# nizal.net
KiCad netlist of a schematic drawn in EAGLE
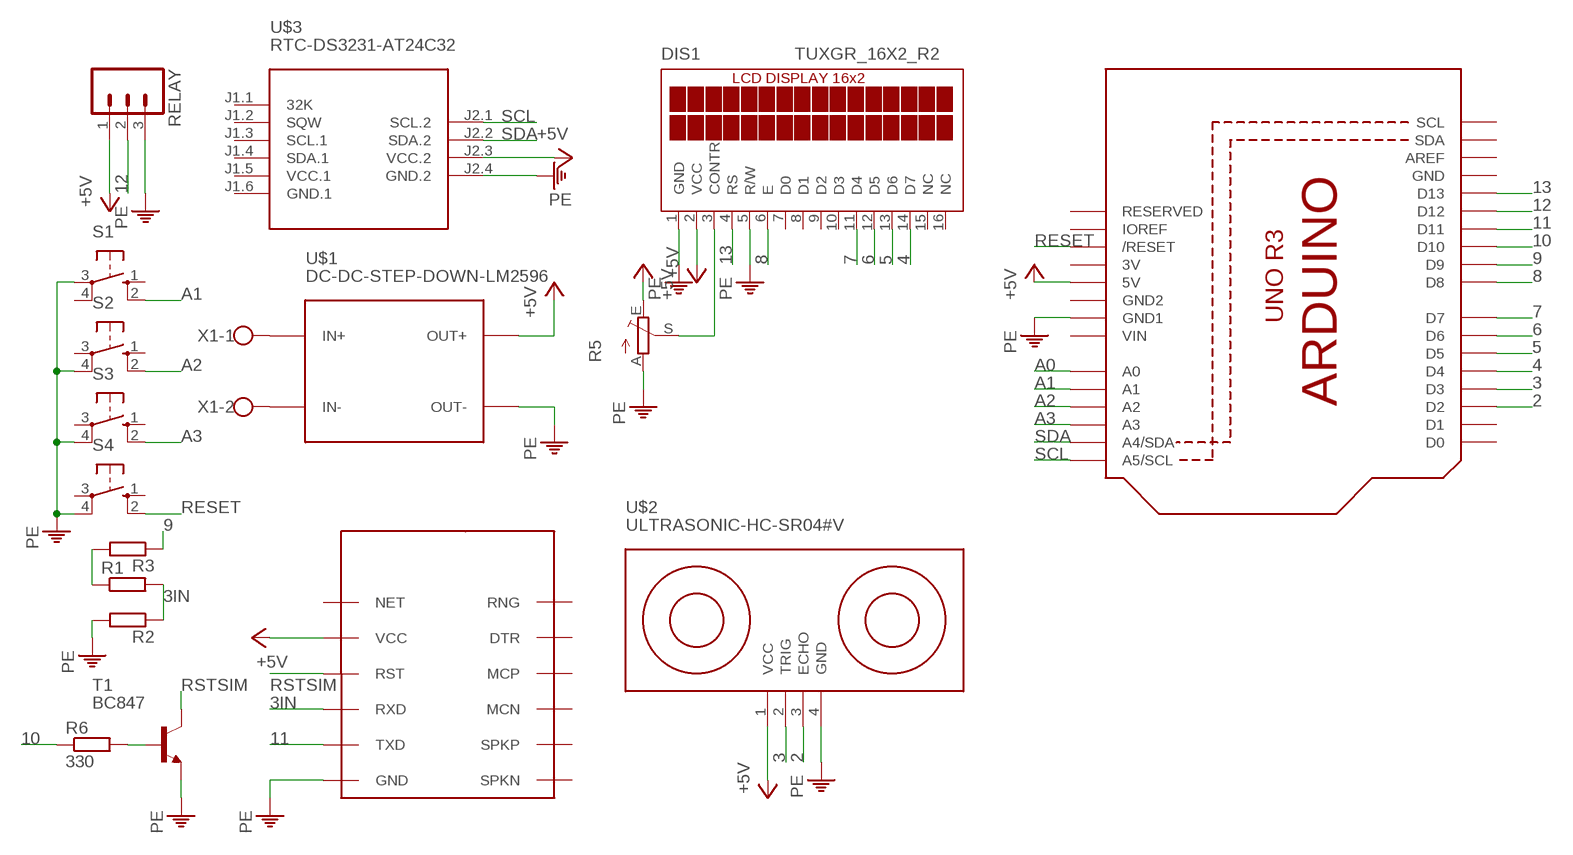
[diagram p0: schematic, sheet 1]

(export (version "E")
  (design (tool "Eeschema 10.0.6"))
  (components
    (comp (ref "DIS1")
      (value "TUXGR_16X2_R2")
      (footprint "eagle-import:TUXGR_16X2_R2")
      (libsource (lib "eagle-import") (part "TUXGR_16X2_R2"))
    )
    (comp (ref "R1")
      (value "R-EU_M0805")
      (footprint "eagle-import:M0805")
      (libsource (lib "eagle-import") (part "R-EU_M0805"))
    )
    (comp (ref "R2")
      (value "R-EU_M0805")
      (footprint "eagle-import:M0805")
      (libsource (lib "eagle-import") (part "R-EU_M0805"))
    )
    (comp (ref "R3")
      (value "R-EU_M0805")
      (footprint "eagle-import:M0805")
      (libsource (lib "eagle-import") (part "R-EU_M0805"))
    )
    (comp (ref "R5")
      (value "TRIM_EU-CA6V")
      (footprint "eagle-import:CA6V")
      (libsource (lib "eagle-import") (part "TRIM_EU-CA6V"))
    )
    (comp (ref "R6")
      (value "330")
      (footprint "eagle-import:M0805")
      (libsource (lib "eagle-import") (part "R-EU_M0805"))
    )
    (comp (ref "RELAY")
      (value "M03")
      (footprint "eagle-import:03P")
      (libsource (lib "eagle-import") (part "M03"))
    )
    (comp (ref "S1")
      (value "10-XX")
      (footprint "eagle-import:B3F-10XX")
      (fields (field (name "MPN") "B3F-1000"))
      (libsource (lib "eagle-import") (part "10-XX"))
    )
    (comp (ref "S2")
      (value "10-XX")
      (footprint "eagle-import:B3F-10XX")
      (fields (field (name "MPN") "B3F-1000"))
      (libsource (lib "eagle-import") (part "10-XX"))
    )
    (comp (ref "S3")
      (value "10-XX")
      (footprint "eagle-import:B3F-10XX")
      (fields (field (name "MPN") "B3F-1000"))
      (libsource (lib "eagle-import") (part "10-XX"))
    )
    (comp (ref "S4")
      (value "10-XX")
      (footprint "eagle-import:B3F-10XX")
      (fields (field (name "MPN") "B3F-1000"))
      (libsource (lib "eagle-import") (part "10-XX"))
    )
    (comp (ref "T1")
      (value "BC847")
      (footprint "eagle-import:SOT23")
      (libsource (lib "eagle-import") (part "BC847"))
    )
    (comp (ref "U$1")
      (value "DC-DC-STEP-DOWN-LM2596")
      (footprint "eagle-import:DC-DC-STEP-DOWN-LM2596")
      (libsource (lib "eagle-import") (part "DC-DC-STEP-DOWN-LM2596"))
    )
    (comp (ref "U$2")
      (value "ULTRASONIC-HC-SR04#V")
      (footprint "eagle-import:ULTRASONIC-HC-SR04#V")
      (libsource (lib "eagle-import") (part "ULTRASONIC-HC-SR04#V"))
    )
    (comp (ref "U$3")
      (value "RTC-DS3231-AT24C32")
      (footprint "eagle-import:RTC-DS3231-AT24C32")
      (libsource (lib "eagle-import") (part "RTC-DS3231-AT24C32"))
    )
    (comp (ref "U$4")
      (value "SIM800L")
      (footprint "eagle-import:SIM-CORE")
      (libsource (lib "eagle-import") (part "SIM800L"))
    )
    (comp (ref "U1")
      (value "ARDUINOR3-DIMENSION")
      (footprint "eagle-import:ARDUINOR3")
      (libsource (lib "eagle-import") (part "ARDUINOR3-DIMENSION"))
    )
    (comp (ref "X1")
      (value "W237-102")
      (footprint "eagle-import:W237-102")
      (fields (field (name "MPN") "237-102"))
      (libsource (lib "eagle-import") (part "W237-102"))
    )
  )
  (nets
    (net (code "1") (name "+5V") (class "Default")
      (node (ref "DIS1") (pin "2") (pinfunction "VCC_2") (pintype "power_in"))
      (node (ref "R5") (pin "E") (pinfunction "E_E") (pintype "passive"))
      (node (ref "RELAY") (pin "1") (pinfunction "1_1") (pintype "passive"))
      (node (ref "U$1") (pin "OUT+") (pinfunction "OUT+_OUT+") (pintype "bidirectional"))
      (node (ref "U$2") (pin "1") (pinfunction "VCC_1") (pintype "power_in"))
      (node (ref "U$3") (pin "J2.3") (pinfunction "VCC.2_J2.3") (pintype "power_in"))
      (node (ref "U$4") (pin "VCC") (pinfunction "VCC_VCC") (pintype "bidirectional"))
      (node (ref "U1") (pin "5V") (pinfunction "5V_5V") (pintype "power_in"))
    )
    (net (code "2") (name "/2") (class "Default")
      (node (ref "U$2") (pin "3") (pinfunction "ECHO_3") (pintype "output"))
      (node (ref "U1") (pin "D2") (pinfunction "D2_D2") (pintype "bidirectional"))
    )
    (net (code "3") (name "/3") (class "Default")
      (node (ref "U$2") (pin "2") (pinfunction "TRIG_2") (pintype "input"))
      (node (ref "U1") (pin "D3") (pinfunction "D3_D3") (pintype "bidirectional"))
    )
    (net (code "4") (name "/3IN") (class "Default")
      (node (ref "R1") (pin "2") (pinfunction "2_2") (pintype "passive"))
      (node (ref "R2") (pin "1") (pinfunction "1_1") (pintype "passive"))
      (node (ref "U$4") (pin "RXD") (pinfunction "RXD_RXD") (pintype "bidirectional"))
    )
    (net (code "5") (name "/3V") (class "Default")
      (node (ref "U1") (pin "3V") (pinfunction "3V_3V") (pintype "power_in"))
    )
    (net (code "6") (name "/4") (class "Default")
      (node (ref "DIS1") (pin "14") (pinfunction "D7_14") (pintype "input"))
      (node (ref "U1") (pin "D4") (pinfunction "D4_D4") (pintype "bidirectional"))
    )
    (net (code "7") (name "/5") (class "Default")
      (node (ref "DIS1") (pin "13") (pinfunction "D6_13") (pintype "input"))
      (node (ref "U1") (pin "D5") (pinfunction "D5_D5") (pintype "bidirectional"))
    )
    (net (code "8") (name "/6") (class "Default")
      (node (ref "DIS1") (pin "12") (pinfunction "D5_12") (pintype "input"))
      (node (ref "U1") (pin "D6") (pinfunction "D6_D6") (pintype "bidirectional"))
    )
    (net (code "9") (name "/7") (class "Default")
      (node (ref "DIS1") (pin "11") (pinfunction "D4_11") (pintype "input"))
      (node (ref "U1") (pin "D7") (pinfunction "D7_D7") (pintype "bidirectional"))
    )
    (net (code "10") (name "/8") (class "Default")
      (node (ref "DIS1") (pin "6") (pinfunction "E_6") (pintype "input"))
      (node (ref "U1") (pin "D8") (pinfunction "D8_D8") (pintype "bidirectional"))
    )
    (net (code "11") (name "/9") (class "Default")
      (node (ref "R3") (pin "1") (pinfunction "1_1") (pintype "passive"))
      (node (ref "U1") (pin "D9") (pinfunction "D9_D9") (pintype "bidirectional"))
    )
    (net (code "12") (name "/10") (class "Default")
      (node (ref "R6") (pin "1") (pinfunction "1_1") (pintype "passive"))
      (node (ref "U1") (pin "D10") (pinfunction "D10_D10") (pintype "bidirectional"))
    )
    (net (code "13") (name "/11") (class "Default")
      (node (ref "U$4") (pin "TXD") (pinfunction "TXD_TXD") (pintype "bidirectional"))
      (node (ref "U1") (pin "D11") (pinfunction "D11_D11") (pintype "bidirectional"))
    )
    (net (code "14") (name "/12") (class "Default")
      (node (ref "RELAY") (pin "2") (pinfunction "2_2") (pintype "passive"))
      (node (ref "U1") (pin "D12") (pinfunction "D12_D12") (pintype "bidirectional"))
    )
    (net (code "15") (name "/13") (class "Default")
      (node (ref "DIS1") (pin "4") (pinfunction "RS_4") (pintype "input"))
      (node (ref "U1") (pin "D13") (pinfunction "D13_D13") (pintype "bidirectional"))
    )
    (net (code "16") (name "/A0") (class "Default")
      (node (ref "U1") (pin "A0") (pinfunction "A0_A0") (pintype "bidirectional"))
    )
    (net (code "17") (name "/A1") (class "Default")
      (node (ref "S1") (pin "2") (pinfunction "S1_2") (pintype "passive"))
      (node (ref "U1") (pin "A1") (pinfunction "A1_A1") (pintype "bidirectional"))
    )
    (net (code "18") (name "/A2") (class "Default")
      (node (ref "S2") (pin "2") (pinfunction "S1_2") (pintype "passive"))
      (node (ref "U1") (pin "A2") (pinfunction "A2_A2") (pintype "bidirectional"))
    )
    (net (code "19") (name "/A3") (class "Default")
      (node (ref "S3") (pin "2") (pinfunction "S1_2") (pintype "passive"))
      (node (ref "U1") (pin "A3") (pinfunction "A3_A3") (pintype "bidirectional"))
    )
    (net (code "20") (name "/GND") (class "Default")
      (node (ref "U1") (pin "GND") (pinfunction "GND_GND") (pintype "power_in"))
    )
    (net (code "21") (name "/GND.1") (class "Default")
      (node (ref "U$3") (pin "J1.6") (pinfunction "GND.1_J1.6") (pintype "power_in"))
    )
    (net (code "22") (name "/GND2") (class "Default")
      (node (ref "U1") (pin "GND2") (pinfunction "GND2_GND2") (pintype "power_in"))
    )
    (net (code "23") (name "/RESET") (class "Default")
      (node (ref "S4") (pin "2") (pinfunction "S1_2") (pintype "passive"))
      (node (ref "U1") (pin "RESET") (pinfunction "/RESET_RESET") (pintype "bidirectional"))
    )
    (net (code "24") (name "/RSTSIM") (class "Default")
      (node (ref "T1") (pin "3") (pinfunction "C_3") (pintype "passive"))
      (node (ref "U$4") (pin "RST") (pinfunction "RST_RST") (pintype "bidirectional"))
    )
    (net (code "25") (name "/SCL") (class "Default")
      (node (ref "U$3") (pin "J2.1") (pinfunction "SCL.2_J2.1") (pintype "bidirectional"))
      (node (ref "U1") (pin "A5") (pinfunction "A5/SCL_A5") (pintype "bidirectional"))
    )
    (net (code "26") (name "/SDA") (class "Default")
      (node (ref "U$3") (pin "J2.2") (pinfunction "SDA.2_J2.2") (pintype "bidirectional"))
      (node (ref "U1") (pin "A4") (pinfunction "A4/SDA_A4") (pintype "bidirectional"))
    )
    (net (code "27") (name "/VCC.1") (class "Default")
      (node (ref "U$3") (pin "J1.5") (pinfunction "VCC.1_J1.5") (pintype "power_in"))
    )
    (net (code "28") (name "/VIN") (class "Default")
      (node (ref "U1") (pin "VIN") (pinfunction "VIN_VIN") (pintype "power_in"))
    )
    (net (code "29") (name "Net-(DIS1-CONTR)") (class "Default")
      (node (ref "DIS1") (pin "3") (pinfunction "CONTR_3") (pintype "input"))
      (node (ref "R5") (pin "S") (pinfunction "S_S") (pintype "passive"))
    )
    (net (code "30") (name "Net-(R1-Pad1)") (class "Default")
      (node (ref "R1") (pin "1") (pinfunction "1_1") (pintype "passive"))
      (node (ref "R3") (pin "2") (pinfunction "2_2") (pintype "passive"))
    )
    (net (code "31") (name "Net-(T1-B)") (class "Default")
      (node (ref "R6") (pin "2") (pinfunction "2_2") (pintype "passive"))
      (node (ref "T1") (pin "1") (pinfunction "B_1") (pintype "passive"))
    )
    (net (code "32") (name "Net-(X1A-KL)") (class "Default")
      (node (ref "U$1") (pin "IN+") (pinfunction "IN+_IN+") (pintype "bidirectional"))
      (node (ref "X1") (pin "1") (pinfunction "KL_1") (pintype "passive"))
    )
    (net (code "33") (name "Net-(X1B-KL)") (class "Default")
      (node (ref "U$1") (pin "IN-") (pinfunction "IN-_IN-") (pintype "bidirectional"))
      (node (ref "X1") (pin "2") (pinfunction "KL_2") (pintype "passive"))
    )
    (net (code "34") (name "PE") (class "Default")
      (node (ref "DIS1") (pin "1") (pinfunction "GND_1") (pintype "power_in"))
      (node (ref "DIS1") (pin "5") (pinfunction "R/W_5") (pintype "input"))
      (node (ref "R2") (pin "2") (pinfunction "2_2") (pintype "passive"))
      (node (ref "R5") (pin "A") (pinfunction "A_A") (pintype "passive"))
      (node (ref "RELAY") (pin "3") (pinfunction "3_3") (pintype "passive"))
      (node (ref "S1") (pin "3") (pinfunction "P_3") (pintype "passive"))
      (node (ref "S2") (pin "4") (pinfunction "P1_4") (pintype "passive"))
      (node (ref "S3") (pin "4") (pinfunction "P1_4") (pintype "passive"))
      (node (ref "S4") (pin "4") (pinfunction "P1_4") (pintype "passive"))
      (node (ref "T1") (pin "2") (pinfunction "E_2") (pintype "passive"))
      (node (ref "U$1") (pin "OUT-") (pinfunction "OUT-_OUT-") (pintype "bidirectional"))
      (node (ref "U$2") (pin "4") (pinfunction "GND_4") (pintype "power_in"))
      (node (ref "U$3") (pin "J2.4") (pinfunction "GND.2_J2.4") (pintype "power_in"))
      (node (ref "U$4") (pin "GND") (pinfunction "GND_GND") (pintype "bidirectional"))
      (node (ref "U1") (pin "GND1") (pinfunction "GND1_GND1") (pintype "power_in"))
    )
    (net (code "35") (name "unconnected-(DIS1-D0-Pad7)") (class "Default")
      (node (ref "DIS1") (pin "7") (pinfunction "D0_7") (pintype "input"))
    )
    (net (code "36") (name "unconnected-(DIS1-D1-Pad8)") (class "Default")
      (node (ref "DIS1") (pin "8") (pinfunction "D1_8") (pintype "input"))
    )
    (net (code "37") (name "unconnected-(DIS1-D2-Pad9)") (class "Default")
      (node (ref "DIS1") (pin "9") (pinfunction "D2_9") (pintype "input"))
    )
    (net (code "38") (name "unconnected-(DIS1-D3-Pad10)") (class "Default")
      (node (ref "DIS1") (pin "10") (pinfunction "D3_10") (pintype "input"))
    )
    (net (code "39") (name "unconnected-(DIS1-NC-Pad15)") (class "Default")
      (node (ref "DIS1") (pin "15") (pinfunction "NC_15") (pintype "no_connect"))
    )
    (net (code "40") (name "unconnected-(DIS1-NC-Pad16)") (class "Default")
      (node (ref "DIS1") (pin "16") (pinfunction "NC_16") (pintype "no_connect"))
    )
    (net (code "41") (name "unconnected-(S1-P1-Pad4)") (class "Default")
      (node (ref "S1") (pin "4") (pinfunction "P1_4") (pintype "passive"))
    )
    (net (code "42") (name "unconnected-(S1-S-Pad1)") (class "Default")
      (node (ref "S1") (pin "1") (pinfunction "S_1") (pintype "passive"))
    )
    (net (code "43") (name "unconnected-(S2-P-Pad3)") (class "Default")
      (node (ref "S2") (pin "3") (pinfunction "P_3") (pintype "passive"))
    )
    (net (code "44") (name "unconnected-(S2-S-Pad1)") (class "Default")
      (node (ref "S2") (pin "1") (pinfunction "S_1") (pintype "passive"))
    )
    (net (code "45") (name "unconnected-(S3-P-Pad3)") (class "Default")
      (node (ref "S3") (pin "3") (pinfunction "P_3") (pintype "passive"))
    )
    (net (code "46") (name "unconnected-(S3-S-Pad1)") (class "Default")
      (node (ref "S3") (pin "1") (pinfunction "S_1") (pintype "passive"))
    )
    (net (code "47") (name "unconnected-(S4-P-Pad3)") (class "Default")
      (node (ref "S4") (pin "3") (pinfunction "P_3") (pintype "passive"))
    )
    (net (code "48") (name "unconnected-(S4-S-Pad1)") (class "Default")
      (node (ref "S4") (pin "1") (pinfunction "S_1") (pintype "passive"))
    )
    (net (code "49") (name "unconnected-(U$3-32K-PadJ1.1)") (class "Default")
      (node (ref "U$3") (pin "J1.1") (pinfunction "32K_J1.1") (pintype "bidirectional"))
    )
    (net (code "50") (name "unconnected-(U$3-SCL.1-PadJ1.3)") (class "Default")
      (node (ref "U$3") (pin "J1.3") (pinfunction "SCL.1_J1.3") (pintype "bidirectional"))
    )
    (net (code "51") (name "unconnected-(U$3-SDA.1-PadJ1.4)") (class "Default")
      (node (ref "U$3") (pin "J1.4") (pinfunction "SDA.1_J1.4") (pintype "bidirectional"))
    )
    (net (code "52") (name "unconnected-(U$3-SQW-PadJ1.2)") (class "Default")
      (node (ref "U$3") (pin "J1.2") (pinfunction "SQW_J1.2") (pintype "bidirectional"))
    )
    (net (code "53") (name "unconnected-(U$4-PadDTR)") (class "Default")
      (node (ref "U$4") (pin "DTR") (pinfunction "DTR_DTR") (pintype "bidirectional"))
    )
    (net (code "54") (name "unconnected-(U$4-PadMCN)") (class "Default")
      (node (ref "U$4") (pin "MCN") (pinfunction "MCN_MCN") (pintype "bidirectional"))
    )
    (net (code "55") (name "unconnected-(U$4-PadMCP)") (class "Default")
      (node (ref "U$4") (pin "MCP") (pinfunction "MCP_MCP") (pintype "bidirectional"))
    )
    (net (code "56") (name "unconnected-(U$4-PadNET)") (class "Default")
      (node (ref "U$4") (pin "NET") (pinfunction "NET_NET") (pintype "bidirectional"))
    )
    (net (code "57") (name "unconnected-(U$4-PadRNG)") (class "Default")
      (node (ref "U$4") (pin "RNG") (pinfunction "RNG_RNG") (pintype "bidirectional"))
    )
    (net (code "58") (name "unconnected-(U$4-PadSPKN)") (class "Default")
      (node (ref "U$4") (pin "SPKN") (pinfunction "SPKN_SPKN") (pintype "bidirectional"))
    )
    (net (code "59") (name "unconnected-(U$4-PadSPKP)") (class "Default")
      (node (ref "U$4") (pin "SPKP") (pinfunction "SPKP_SPKP") (pintype "bidirectional"))
    )
    (net (code "60") (name "unconnected-(U1-PadAREF)") (class "Default")
      (node (ref "U1") (pin "AREF") (pinfunction "AREF_AREF") (pintype "bidirectional"))
    )
    (net (code "61") (name "unconnected-(U1-PadD0)") (class "Default")
      (node (ref "U1") (pin "D0") (pinfunction "D0_D0") (pintype "bidirectional"))
    )
    (net (code "62") (name "unconnected-(U1-PadD1)") (class "Default")
      (node (ref "U1") (pin "D1") (pinfunction "D1_D1") (pintype "bidirectional"))
    )
    (net (code "63") (name "unconnected-(U1-PadIOREF)") (class "Default")
      (node (ref "U1") (pin "IOREF") (pinfunction "IOREF_IOREF") (pintype "output"))
    )
    (net (code "64") (name "unconnected-(U1-PadRESERVED)") (class "Default")
      (node (ref "U1") (pin "RESERVED") (pinfunction "RESERVED_RESERVED") (pintype "no_connect"))
    )
    (net (code "65") (name "unconnected-(U1-PadSCL)") (class "Default")
      (node (ref "U1") (pin "SCL") (pinfunction "SCL_SCL") (pintype "bidirectional"))
    )
    (net (code "66") (name "unconnected-(U1-PadSDA)") (class "Default")
      (node (ref "U1") (pin "SDA") (pinfunction "SDA_SDA") (pintype "bidirectional"))
    )
  )
)
